# 2OR_2.net
KiCad netlist of a schematic drawn in EAGLE
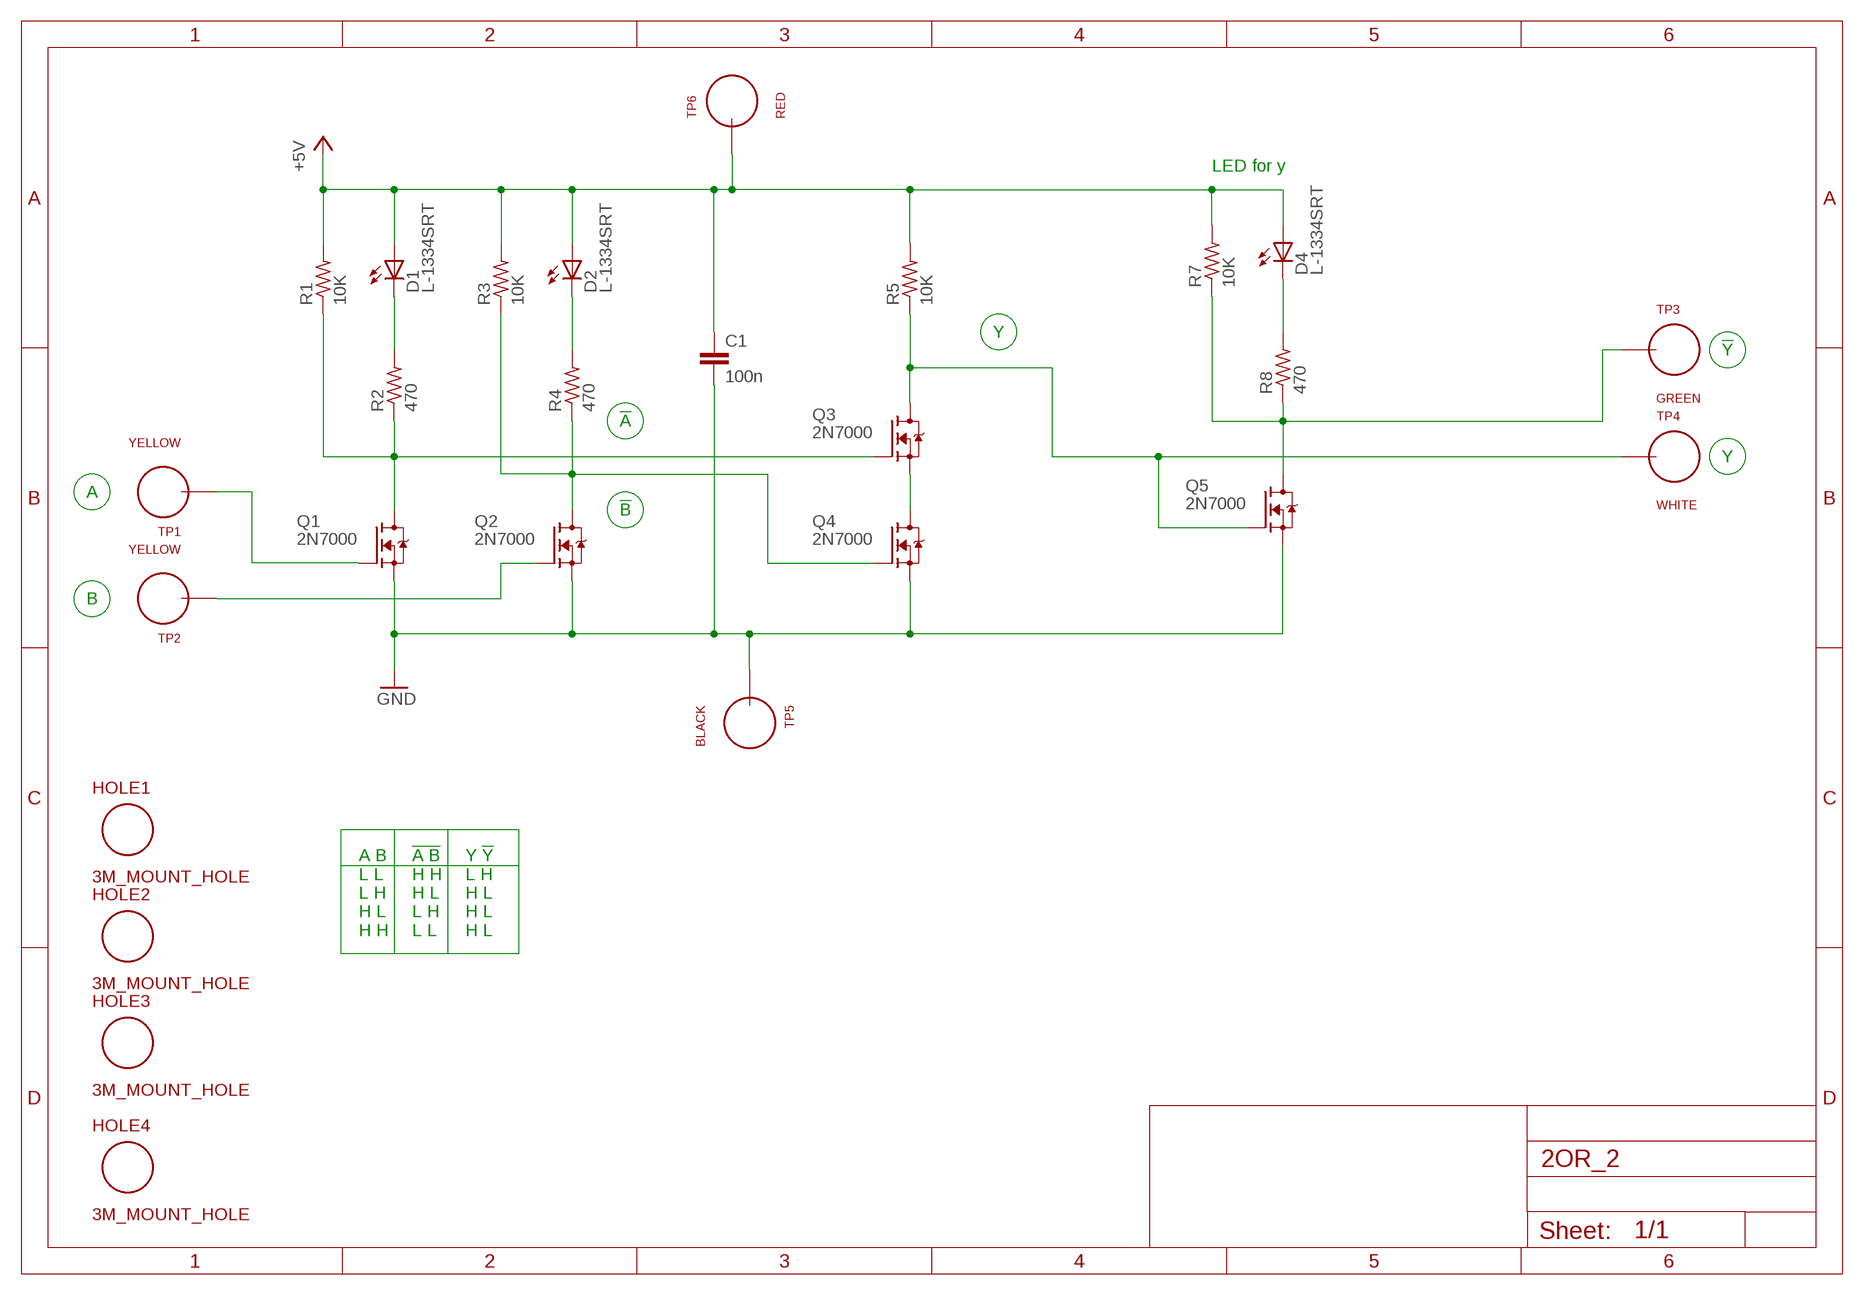
[diagram p0: schematic, sheet 1]

(export (version "E")
  (design (tool "Eeschema 10.0.6"))
  (components
    (comp (ref "C1")
      (value "100n")
      (footprint "eagle-import:CAP_P2INCH")
      (libsource (lib "eagle-import") (part "C_P2INCH"))
    )
    (comp (ref "D1")
      (value "L-1334SRT")
      (footprint "eagle-import:LED3MM")
      (libsource (lib "eagle-import") (part "L-1334SRT"))
    )
    (comp (ref "D2")
      (value "L-1334SRT")
      (footprint "eagle-import:LED3MM")
      (libsource (lib "eagle-import") (part "L-1334SRT"))
    )
    (comp (ref "D4")
      (value "L-1334SRT")
      (footprint "eagle-import:LED3MM")
      (libsource (lib "eagle-import") (part "L-1334SRT"))
    )
    (comp (ref "HOLE1")
      (value "3M_MOUNT_HOLE")
      (footprint "eagle-import:3M_HOLE")
      (libsource (lib "eagle-import") (part "3M_MOUNT_HOLE"))
    )
    (comp (ref "HOLE2")
      (value "3M_MOUNT_HOLE")
      (footprint "eagle-import:3M_HOLE")
      (libsource (lib "eagle-import") (part "3M_MOUNT_HOLE"))
    )
    (comp (ref "HOLE3")
      (value "3M_MOUNT_HOLE")
      (footprint "eagle-import:3M_HOLE")
      (libsource (lib "eagle-import") (part "3M_MOUNT_HOLE"))
    )
    (comp (ref "HOLE4")
      (value "3M_MOUNT_HOLE")
      (footprint "eagle-import:3M_HOLE")
      (libsource (lib "eagle-import") (part "3M_MOUNT_HOLE"))
    )
    (comp (ref "Q1")
      (value "2N7000")
      (footprint "eagle-import:TO92-DGS")
      (libsource (lib "eagle-import") (part "2N7000"))
    )
    (comp (ref "Q2")
      (value "2N7000")
      (footprint "eagle-import:TO92-DGS")
      (libsource (lib "eagle-import") (part "2N7000"))
    )
    (comp (ref "Q3")
      (value "2N7000")
      (footprint "eagle-import:TO92-DGS")
      (libsource (lib "eagle-import") (part "2N7000"))
    )
    (comp (ref "Q4")
      (value "2N7000")
      (footprint "eagle-import:TO92-DGS")
      (libsource (lib "eagle-import") (part "2N7000"))
    )
    (comp (ref "Q5")
      (value "2N7000")
      (footprint "eagle-import:TO92-DGS")
      (libsource (lib "eagle-import") (part "2N7000"))
    )
    (comp (ref "R1")
      (value "10K")
      (footprint "eagle-import:R_P2INCH")
      (libsource (lib "eagle-import") (part "R_P2INCH"))
    )
    (comp (ref "R2")
      (value "470")
      (footprint "eagle-import:R_P2INCH")
      (libsource (lib "eagle-import") (part "R_P2INCH"))
    )
    (comp (ref "R3")
      (value "10K")
      (footprint "eagle-import:R_P2INCH")
      (libsource (lib "eagle-import") (part "R_P2INCH"))
    )
    (comp (ref "R4")
      (value "470")
      (footprint "eagle-import:R_P2INCH")
      (libsource (lib "eagle-import") (part "R_P2INCH"))
    )
    (comp (ref "R5")
      (value "10K")
      (footprint "eagle-import:R_P2INCH")
      (libsource (lib "eagle-import") (part "R_P2INCH"))
    )
    (comp (ref "R7")
      (value "10K")
      (footprint "eagle-import:R_P2INCH")
      (libsource (lib "eagle-import") (part "R_P2INCH"))
    )
    (comp (ref "R8")
      (value "470")
      (footprint "eagle-import:R_P2INCH")
      (libsource (lib "eagle-import") (part "R_P2INCH"))
    )
    (comp (ref "TP1")
      (value "YELLOW")
      (footprint "eagle-import:TEST_LOOP")
      (libsource (lib "eagle-import") (part "TEST_LOOP"))
    )
    (comp (ref "TP2")
      (value "YELLOW")
      (footprint "eagle-import:TEST_LOOP")
      (libsource (lib "eagle-import") (part "TEST_LOOP"))
    )
    (comp (ref "TP3")
      (value "GREEN")
      (footprint "eagle-import:TEST_LOOP")
      (libsource (lib "eagle-import") (part "TEST_LOOP"))
    )
    (comp (ref "TP4")
      (value "WHITE")
      (footprint "eagle-import:TEST_LOOP")
      (libsource (lib "eagle-import") (part "TEST_LOOP"))
    )
    (comp (ref "TP5")
      (value "BLACK")
      (footprint "eagle-import:TEST_LOOP")
      (libsource (lib "eagle-import") (part "TEST_LOOP"))
    )
    (comp (ref "TP6")
      (value "RED")
      (footprint "eagle-import:TEST_LOOP")
      (libsource (lib "eagle-import") (part "TEST_LOOP"))
    )
  )
  (nets
    (net (code "1") (name "+5V") (class "Default")
      (node (ref "C1") (pin "1") (pinfunction "1_1") (pintype "passive"))
      (node (ref "D1") (pin "A") (pinfunction "A_A") (pintype "passive"))
      (node (ref "D2") (pin "A") (pinfunction "A_A") (pintype "passive"))
      (node (ref "D4") (pin "A") (pinfunction "A_A") (pintype "passive"))
      (node (ref "R1") (pin "2") (pinfunction "2_2") (pintype "passive"))
      (node (ref "R3") (pin "2") (pinfunction "2_2") (pintype "passive"))
      (node (ref "R5") (pin "2") (pinfunction "2_2") (pintype "passive"))
      (node (ref "R7") (pin "2") (pinfunction "2_2") (pintype "passive"))
      (node (ref "TP6") (pin "P$1") (pinfunction "P$1_P$1") (pintype "bidirectional"))
    )
    (net (code "2") (name "GND") (class "Default")
      (node (ref "C1") (pin "2") (pinfunction "2_2") (pintype "passive"))
      (node (ref "Q1") (pin "S") (pinfunction "S_S") (pintype "passive"))
      (node (ref "Q2") (pin "S") (pinfunction "S_S") (pintype "passive"))
      (node (ref "Q4") (pin "S") (pinfunction "S_S") (pintype "passive"))
      (node (ref "Q5") (pin "S") (pinfunction "S_S") (pintype "passive"))
      (node (ref "TP5") (pin "P$1") (pinfunction "P$1_P$1") (pintype "bidirectional"))
    )
    (net (code "3") (name "Net-(D1-C)") (class "Default")
      (node (ref "D1") (pin "K") (pinfunction "C_K") (pintype "passive"))
      (node (ref "R2") (pin "2") (pinfunction "2_2") (pintype "passive"))
    )
    (net (code "4") (name "Net-(D2-C)") (class "Default")
      (node (ref "D2") (pin "K") (pinfunction "C_K") (pintype "passive"))
      (node (ref "R4") (pin "2") (pinfunction "2_2") (pintype "passive"))
    )
    (net (code "5") (name "Net-(D4-C)") (class "Default")
      (node (ref "D4") (pin "K") (pinfunction "C_K") (pintype "passive"))
      (node (ref "R8") (pin "2") (pinfunction "2_2") (pintype "passive"))
    )
    (net (code "6") (name "Net-(Q1-PadD)") (class "Default")
      (node (ref "Q1") (pin "D") (pinfunction "D_D") (pintype "passive"))
      (node (ref "Q3") (pin "G") (pinfunction "G_G") (pintype "passive"))
      (node (ref "R1") (pin "1") (pinfunction "1_1") (pintype "passive"))
      (node (ref "R2") (pin "1") (pinfunction "1_1") (pintype "passive"))
    )
    (net (code "7") (name "Net-(Q1-PadG)") (class "Default")
      (node (ref "Q1") (pin "G") (pinfunction "G_G") (pintype "passive"))
      (node (ref "TP1") (pin "P$1") (pinfunction "P$1_P$1") (pintype "bidirectional"))
    )
    (net (code "8") (name "Net-(Q2-PadD)") (class "Default")
      (node (ref "Q2") (pin "D") (pinfunction "D_D") (pintype "passive"))
      (node (ref "Q4") (pin "G") (pinfunction "G_G") (pintype "passive"))
      (node (ref "R3") (pin "1") (pinfunction "1_1") (pintype "passive"))
      (node (ref "R4") (pin "1") (pinfunction "1_1") (pintype "passive"))
    )
    (net (code "9") (name "Net-(Q2-PadG)") (class "Default")
      (node (ref "Q2") (pin "G") (pinfunction "G_G") (pintype "passive"))
      (node (ref "TP2") (pin "P$1") (pinfunction "P$1_P$1") (pintype "bidirectional"))
    )
    (net (code "10") (name "Net-(Q3-PadD)") (class "Default")
      (node (ref "Q3") (pin "D") (pinfunction "D_D") (pintype "passive"))
      (node (ref "Q5") (pin "G") (pinfunction "G_G") (pintype "passive"))
      (node (ref "R5") (pin "1") (pinfunction "1_1") (pintype "passive"))
      (node (ref "TP4") (pin "P$1") (pinfunction "P$1_P$1") (pintype "bidirectional"))
    )
    (net (code "11") (name "Net-(Q3-PadS)") (class "Default")
      (node (ref "Q3") (pin "S") (pinfunction "S_S") (pintype "passive"))
      (node (ref "Q4") (pin "D") (pinfunction "D_D") (pintype "passive"))
    )
    (net (code "12") (name "Net-(Q5-PadD)") (class "Default")
      (node (ref "Q5") (pin "D") (pinfunction "D_D") (pintype "passive"))
      (node (ref "R7") (pin "1") (pinfunction "1_1") (pintype "passive"))
      (node (ref "R8") (pin "1") (pinfunction "1_1") (pintype "passive"))
      (node (ref "TP3") (pin "P$1") (pinfunction "P$1_P$1") (pintype "bidirectional"))
    )
  )
)
